# JN5168.net
KiCad netlist of a schematic drawn in Altium Designer
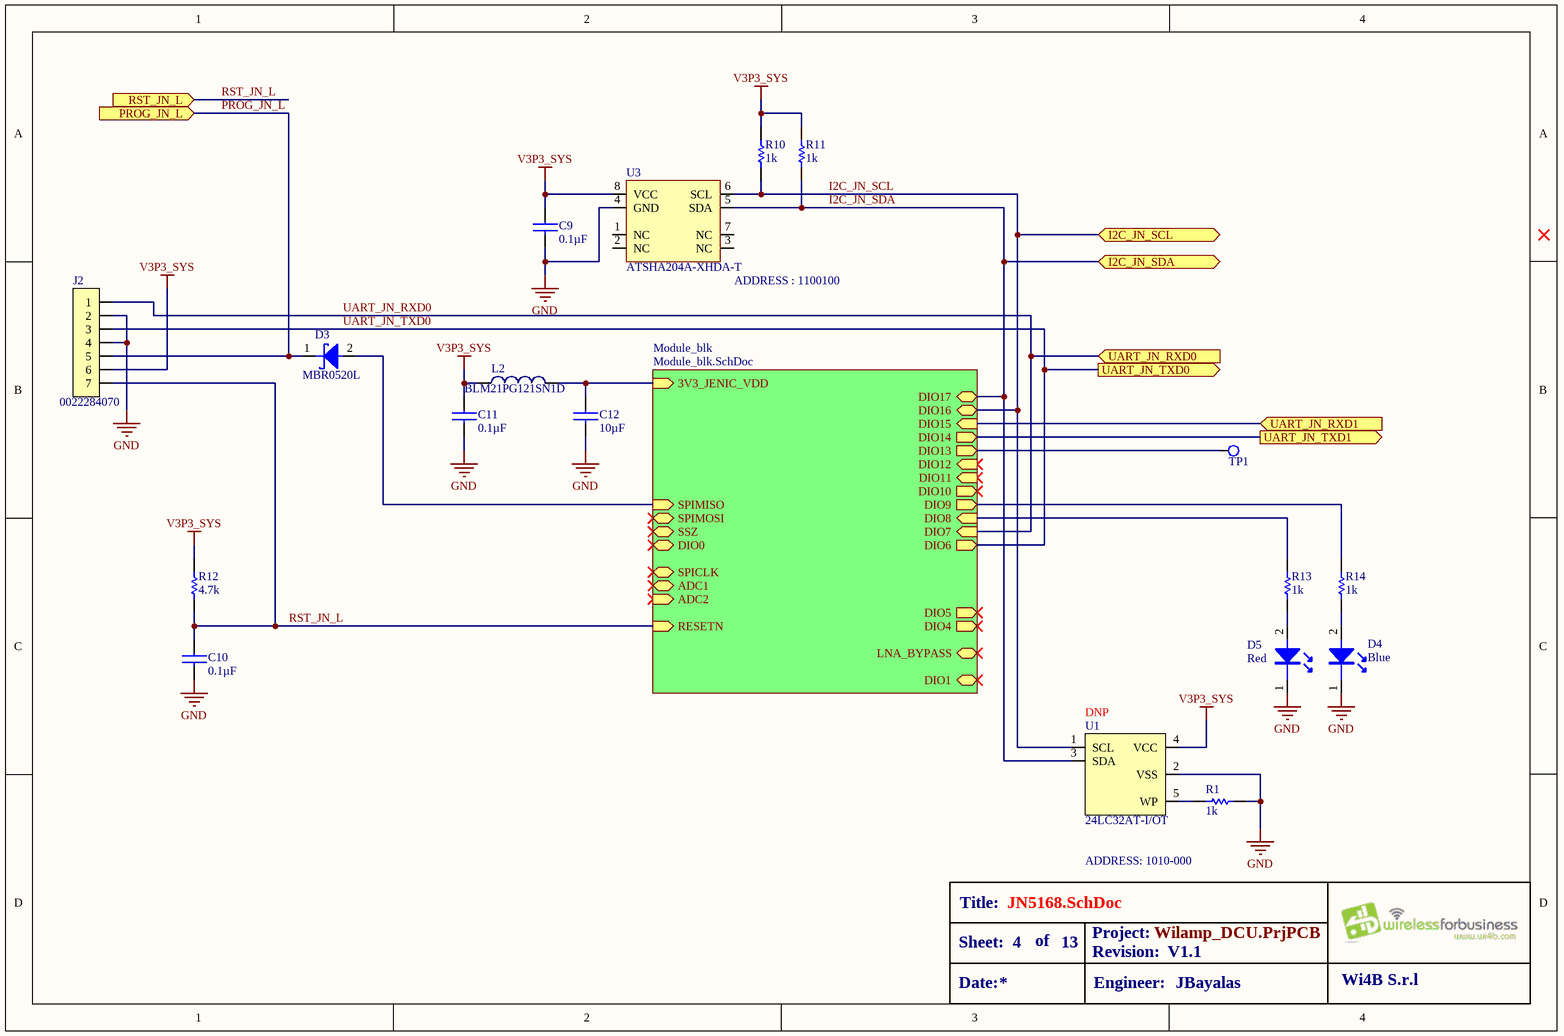
[diagram p0: JN5168.SchDoc]

(export (version "E")
  (design (tool "Eeschema 10.0.6"))
  (components
    (comp (ref "C9")
      (value "0.1µF")
      (footprint "C0402")
      (description "CAP CER 0.1UF 16V X7R 0402")
      (fields (field (name "MPN") "CL05B104KO3LNNC"))
      (libsource (lib "Capacitor") (part "CL05B104KO3LNNC"))
    )
    (comp (ref "C10")
      (value "0.1µF")
      (footprint "C0402")
      (description "CAP CER 0.1UF 16V X7R 0402")
      (fields (field (name "MPN") "CL05B104KO3LNNC"))
      (libsource (lib "Capacitor") (part "CL05B104KO3LNNC"))
    )
    (comp (ref "C11")
      (value "0.1µF")
      (footprint "C0402")
      (description "CAP CER 0.1UF 16V X7R 0402")
      (fields (field (name "MPN") "CL05B104KO3LNNC"))
      (libsource (lib "Capacitor") (part "CL05B104KO3LNNC"))
    )
    (comp (ref "C12")
      (value "10µF")
      (footprint "C0805")
      (description "CAP CER 10UF 6.3V X5R 0805")
      (fields (field (name "MPN") "GRM219R60J106KE19D"))
      (libsource (lib "Capacitor") (part "GRM219R60J106KE19D"))
    )
    (comp (ref "D3")
      (value "MBR0520L")
      (footprint "SOD123")
      (description "DIODE SCHOTTKY 20V 0.5A SOD123")
      (fields (field (name "MPN") "MBR0520L"))
      (libsource (lib "Diode") (part "MBR0520L"))
    )
    (comp (ref "D4")
      (value "Blue")
      (footprint "LED-0603 (BLUE)")
      (description "LED BLUE CLEAR 0603 SMD")
      (fields (field (name "MPN") "LTST-C191TBKT"))
      (libsource (lib "Diode") (part "LTST-C191TBKT"))
    )
    (comp (ref "D5")
      (value "Red")
      (footprint "LED0805 - (RED)")
      (description "LED CHIPLED 633NM RED 0805 SMD")
      (fields (field (name "MPN") "LS R976-NR-1"))
      (libsource (lib "Diode") (part "LS R976-NR-1"))
    )
    (comp (ref "J2")
      (value "*")
      (footprint "0022284070")
      (description "CONN HEADER 7POS .100 VERT TIN")
      (fields (field (name "MPN") "0022284070"))
      (libsource (lib "Connector") (part "0022284070"))
    )
    (comp (ref "L2")
      (value "*")
      (footprint "0805 INDUCTOR")
      (description "FERRITE CHIP 120 OHM 0805")
      (fields (field (name "MPN") "BLM21PG121SN1D"))
      (libsource (lib "Inductor") (part "BLM21PG121SN1D"))
    )
    (comp (ref "R1")
      (value "1k")
      (footprint "R0402")
      (description "RES SMD 1K OHM 1% 1/10W 0402")
      (fields (field (name "MPN") "MCS04020C1001FE000"))
      (libsource (lib "Res") (part "MCS04020C1001FE000"))
    )
    (comp (ref "R10")
      (value "1k")
      (footprint "R0402")
      (description "RES SMD 1K OHM 1% 1/10W 0402")
      (fields (field (name "MPN") "MCS04020C1001FE000"))
      (libsource (lib "Res") (part "MCS04020C1001FE000"))
    )
    (comp (ref "R11")
      (value "1k")
      (footprint "R0402")
      (description "RES SMD 1K OHM 1% 1/10W 0402")
      (fields (field (name "MPN") "MCS04020C1001FE000"))
      (libsource (lib "Res") (part "MCS04020C1001FE000"))
    )
    (comp (ref "R12")
      (value "4.7k")
      (footprint "R0603")
      (description "RES SMD 4.7K OHM 0.1% 1/10W 0603")
      (fields (field (name "MPN") "ERA-3AEB472V"))
      (libsource (lib "Res") (part "ERA-3AEB472V"))
    )
    (comp (ref "R13")
      (value "1k")
      (footprint "R0603")
      (description "RES SMD 1K OHM 1% 1/10W 0603")
      (fields (field (name "MPN") "ERJ-3EKF1001V"))
      (libsource (lib "Res") (part "ERJ-3EKF1001V"))
    )
    (comp (ref "R14")
      (value "1k")
      (footprint "R0603")
      (description "RES SMD 1K OHM 1% 1/10W 0603")
      (fields (field (name "MPN") "ERJ-3EKF1001V"))
      (libsource (lib "Res") (part "ERJ-3EKF1001V"))
    )
    (comp (ref "TP1")
      (value "*")
      (footprint "Test Point 1.27mm")
      (description "Test Point 1.27mm")
      (libsource (lib "Miscellaneous") (part "Test Point"))
    )
    (comp (ref "U1")
      (value "*")
      (footprint "SOT-23-5")
      (description "IC EEPROM 32KBIT 400KHZ SOT23-5")
      (fields (field (name "LOAD") "DNP") (field (name "MPN") "24LC32AT-I/OT"))
      (libsource (lib "IC") (part "24LC32AT-I/OT"))
    )
    (comp (ref "U3")
      (value "ATSHA204A-XHDA-T")
      (footprint "TSSOP-8 (wide Body)")
      (description "IC CRYPTO 4.5KB I2C")
      (fields (field (name "MPN") "ATSHA204A-XHDA-T"))
      (libsource (lib "IC") (part "ATSHA204A-XHDA-T"))
    )
  )
  (nets
    (net (code "1") (name "/3V3_JENIC_VDD") (class "Default")
      (node (ref "C12") (pin "1") (pinfunction "1_1") (pintype "passive"))
      (node (ref "L2") (pin "1") (pinfunction "1_1") (pintype "passive"))
    )
    (net (code "8") (name "/DIO8") (class "Default")
      (node (ref "R13") (pin "1") (pinfunction "1_1") (pintype "passive"))
    )
    (net (code "9") (name "/DIO9") (class "Default")
      (node (ref "R14") (pin "1") (pinfunction "1_1") (pintype "passive"))
    )
    (net (code "13") (name "/DIO13") (class "Default")
      (node (ref "TP1") (pin "1") (pinfunction "1_1") (pintype "passive"))
    )
    (net (code "14") (name "/I2C_JN_SCL") (class "Default")
      (node (ref "R10") (pin "1") (pinfunction "1_1") (pintype "passive"))
      (node (ref "U1") (pin "1") (pinfunction "SCL_1") (pintype "passive"))
      (node (ref "U3") (pin "6") (pinfunction "SCL_6") (pintype "passive"))
    )
    (net (code "15") (name "/I2C_JN_SDA") (class "Default")
      (node (ref "R11") (pin "1") (pinfunction "1_1") (pintype "passive"))
      (node (ref "U1") (pin "3") (pinfunction "SDA_3") (pintype "passive"))
      (node (ref "U3") (pin "5") (pinfunction "SDA_5") (pintype "passive"))
    )
    (net (code "17") (name "/PROG_JN_L") (class "Default")
      (node (ref "D3") (pin "1") (pinfunction "cathode_1") (pintype "passive"))
      (node (ref "J2") (pin "5") (pinfunction "5_5") (pintype "passive"))
    )
    (net (code "18") (name "/RST_JN_L") (class "Default")
      (node (ref "C10") (pin "1") (pinfunction "1_1") (pintype "passive"))
      (node (ref "J2") (pin "7") (pinfunction "7_7") (pintype "passive"))
      (node (ref "R12") (pin "1") (pinfunction "1_1") (pintype "passive"))
    )
    (net (code "20") (name "/SPIMISO") (class "Default")
      (node (ref "D3") (pin "2") (pinfunction "anode_2") (pintype "passive"))
    )
    (net (code "23") (name "/UART_JN_RXD0") (class "Default")
      (node (ref "J2") (pin "1") (pinfunction "1_1") (pintype "passive"))
    )
    (net (code "25") (name "/UART_JN_TXD0") (class "Default")
      (node (ref "J2") (pin "3") (pinfunction "3_3") (pintype "passive"))
    )
    (net (code "27") (name "GND") (class "Default")
      (node (ref "C10") (pin "2") (pinfunction "2_2") (pintype "passive"))
      (node (ref "C11") (pin "2") (pinfunction "2_2") (pintype "passive"))
      (node (ref "C12") (pin "2") (pinfunction "2_2") (pintype "passive"))
      (node (ref "C9") (pin "2") (pinfunction "2_2") (pintype "passive"))
      (node (ref "D4") (pin "1") (pinfunction "1_1") (pintype "passive"))
      (node (ref "D5") (pin "1") (pinfunction "1_1") (pintype "passive"))
      (node (ref "J2") (pin "2") (pinfunction "2_2") (pintype "passive"))
      (node (ref "J2") (pin "4") (pinfunction "4_4") (pintype "passive"))
      (node (ref "R1") (pin "2") (pinfunction "2_2") (pintype "passive"))
      (node (ref "U1") (pin "2") (pinfunction "VSS_2") (pintype "passive"))
      (node (ref "U3") (pin "4") (pinfunction "GND_4") (pintype "passive"))
    )
    (net (code "28") (name "Net-(D4-Pad2)") (class "Default")
      (node (ref "D4") (pin "2") (pinfunction "2_2") (pintype "passive"))
      (node (ref "R14") (pin "2") (pinfunction "2_2") (pintype "passive"))
    )
    (net (code "29") (name "Net-(D5-Pad2)") (class "Default")
      (node (ref "D5") (pin "2") (pinfunction "2_2") (pintype "passive"))
      (node (ref "R13") (pin "2") (pinfunction "2_2") (pintype "passive"))
    )
    (net (code "30") (name "Net-(U1-WP)") (class "Default")
      (node (ref "R1") (pin "1") (pinfunction "1_1") (pintype "passive"))
      (node (ref "U1") (pin "5") (pinfunction "WP_5") (pintype "passive"))
    )
    (net (code "31") (name "V3P3_SYS") (class "Default")
      (node (ref "C11") (pin "1") (pinfunction "1_1") (pintype "passive"))
      (node (ref "C9") (pin "1") (pinfunction "1_1") (pintype "passive"))
      (node (ref "J2") (pin "6") (pinfunction "6_6") (pintype "passive"))
      (node (ref "L2") (pin "2") (pinfunction "2_2") (pintype "passive"))
      (node (ref "R10") (pin "2") (pinfunction "2_2") (pintype "passive"))
      (node (ref "R11") (pin "2") (pinfunction "2_2") (pintype "passive"))
      (node (ref "R12") (pin "2") (pinfunction "2_2") (pintype "passive"))
      (node (ref "U1") (pin "4") (pinfunction "VCC_4") (pintype "passive"))
      (node (ref "U3") (pin "8") (pinfunction "VCC_8") (pintype "passive"))
    )
    (net (code "32") (name "unconnected-(U3-NC-Pad1)") (class "Default")
      (node (ref "U3") (pin "1") (pinfunction "NC_1") (pintype "passive"))
    )
    (net (code "33") (name "unconnected-(U3-NC-Pad2)") (class "Default")
      (node (ref "U3") (pin "2") (pinfunction "NC_2") (pintype "passive"))
    )
    (net (code "34") (name "unconnected-(U3-NC-Pad3)") (class "Default")
      (node (ref "U3") (pin "3") (pinfunction "NC_3") (pintype "passive"))
    )
    (net (code "35") (name "unconnected-(U3-NC-Pad7)") (class "Default")
      (node (ref "U3") (pin "7") (pinfunction "NC_7") (pintype "passive"))
    )
  )
)
